# MAGIsDebugger.net
KiCad netlist of a schematic drawn in Altium Designer
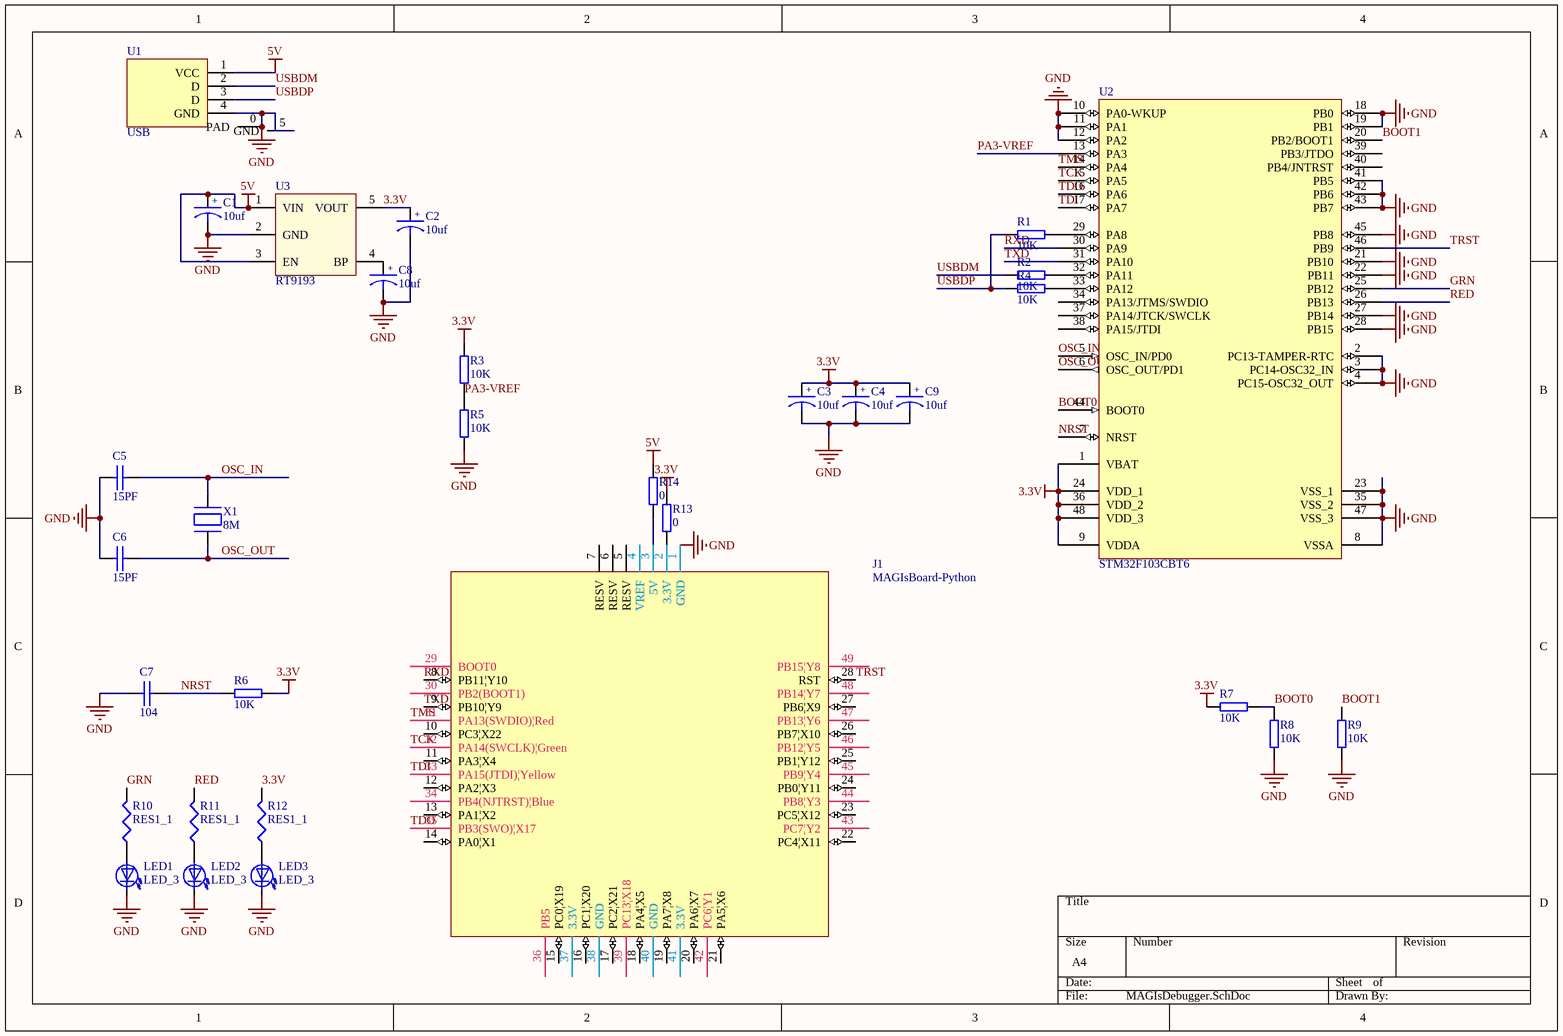
[diagram p0: MAGIsDebugger.SchDoc]

(export (version "E")
  (design (tool "Eeschema 10.0.6"))
  (components
    (comp (ref "C1")
      (value "10uf")
      (footprint "6-0805_n")
      (description "Capacitor")
      (libsource (lib "电容器") (part "CAPACITOR POL"))
    )
    (comp (ref "C2")
      (value "10uf")
      (footprint "6-0805_n")
      (description "Capacitor")
      (libsource (lib "电容器") (part "CAPACITOR POL"))
    )
    (comp (ref "C3")
      (value "10uf")
      (footprint "6-0805_n")
      (description "Capacitor")
      (libsource (lib "电容器") (part "CAPACITOR POL"))
    )
    (comp (ref "C4")
      (value "10uf")
      (footprint "6-0805_N")
      (description "Capacitor")
      (libsource (lib "电容器") (part "CAPACITOR POL"))
    )
    (comp (ref "C5") (value "15PF") (footprint "6-0805_n") (libsource (lib "STM32") (part "CAP")))
    (comp (ref "C6") (value "15PF") (footprint "6-0805_n") (libsource (lib "STM32") (part "CAP")))
    (comp (ref "C7") (value "104") (footprint "6-0805_n") (libsource (lib "STM32") (part "CAP")))
    (comp (ref "C8")
      (value "10uf")
      (footprint "6-0805_n")
      (description "Capacitor")
      (libsource (lib "电容器") (part "CAPACITOR POL"))
    )
    (comp (ref "C9")
      (value "10uf")
      (footprint "6-0805_N")
      (description "Capacitor")
      (libsource (lib "电容器") (part "CAPACITOR POL"))
    )
    (comp (ref "J1")
      (value "MAGIsBoard-Python")
      (footprint "MAGIsBoard-Python")
      (libsource (lib "MAGIsBoard") (part "MAGIsBoard-Python"))
    )
    (comp (ref "LED1") (value "LED_3") (footprint "6-0805_n") (libsource (lib "二极管") (part "LED_3")))
    (comp (ref "LED2") (value "LED_3") (footprint "6-0805_n") (libsource (lib "二极管") (part "LED_3")))
    (comp (ref "LED3") (value "LED_3") (footprint "6-0805_n") (libsource (lib "二极管") (part "LED_3")))
    (comp (ref "R1") (value "10K") (footprint "6-0805_n") (libsource (lib "STM32") (part "RES")))
    (comp (ref "R2") (value "10K") (footprint "6-0805_n") (libsource (lib "STM32") (part "RES")))
    (comp (ref "R3") (value "10K") (footprint "6-0805_n") (libsource (lib "STM32") (part "RES")))
    (comp (ref "R4") (value "10K") (footprint "6-0805_n") (libsource (lib "STM32") (part "RES")))
    (comp (ref "R5") (value "10K") (footprint "6-0805_n") (libsource (lib "STM32") (part "RES")))
    (comp (ref "R6") (value "10K") (footprint "6-0805_n") (libsource (lib "STM32") (part "RES")))
    (comp (ref "R7") (value "10K") (footprint "6-0805_n") (libsource (lib "STM32") (part "RES")))
    (comp (ref "R8") (value "10K") (footprint "6-0805_n") (libsource (lib "STM32") (part "RES")))
    (comp (ref "R9") (value "10K") (footprint "6-0805_n") (libsource (lib "STM32") (part "RES")))
    (comp (ref "R10") (value "RES1_1") (footprint "6-0805_n") (libsource (lib "电阻器") (part "RES1_1")))
    (comp (ref "R11") (value "RES1_1") (footprint "6-0805_n") (libsource (lib "电阻器") (part "RES1_1")))
    (comp (ref "R12") (value "RES1_1") (footprint "6-0805_n") (libsource (lib "电阻器") (part "RES1_1")))
    (comp (ref "R13") (value "0") (footprint "6-0805_n") (libsource (lib "STM32") (part "RES")))
    (comp (ref "R14") (value "0") (footprint "6-0805_n") (libsource (lib "STM32") (part "RES")))
    (comp (ref "U1") (value "USB") (footprint "MicroUSB-B") (libsource (lib "USB接口") (part "USB")))
    (comp (ref "U2")
      (value "STM32F103CBT6")
      (footprint "LQFP48_N")
      (description "STM32 ARM-based 32-bit MCU with 128 Kbytes Flash, 48-pin LQFP, Industrial Temperature")
      (fields (field (name "PUBLISHER") "Altium Limited"))
      (libsource (lib "ST Microcontroller 32-Bit STM32") (part "STM32F103CBT6"))
    )
    (comp (ref "U3") (value "RT9193") (footprint "RT9193") (libsource (lib "PMIC") (part "RT9193")))
    (comp (ref "X1") (value "8M") (footprint "5032") (libsource (lib "STM32") (part "CRYSTAL")))
  )
  (nets
    (net (code "1") (name "/BOOT0") (class "Default")
      (node (ref "R7") (pin "1") (pinfunction "1_1") (pintype "passive"))
      (node (ref "R8") (pin "2") (pinfunction "2_2") (pintype "passive"))
      (node (ref "U2") (pin "44") (pinfunction "BOOT0_44") (pintype "input"))
    )
    (net (code "2") (name "/BOOT1") (class "Default")
      (node (ref "R9") (pin "2") (pinfunction "2_2") (pintype "passive"))
      (node (ref "U2") (pin "20") (pinfunction "PB2/BOOT1_20") (pintype "bidirectional"))
    )
    (net (code "3") (name "/GRN") (class "Default")
      (node (ref "R10") (pin "2") (pinfunction "2_2") (pintype "passive"))
      (node (ref "U2") (pin "25") (pinfunction "PB12_25") (pintype "bidirectional"))
    )
    (net (code "4") (name "/NRST") (class "Default")
      (node (ref "C7") (pin "2") (pinfunction "2_2") (pintype "passive"))
      (node (ref "R6") (pin "1") (pinfunction "1_1") (pintype "passive"))
      (node (ref "U2") (pin "7") (pinfunction "NRST_7") (pintype "bidirectional"))
    )
    (net (code "5") (name "/OSC_IN") (class "Default")
      (node (ref "C5") (pin "2") (pinfunction "2_2") (pintype "passive"))
      (node (ref "U2") (pin "5") (pinfunction "OSC_IN/PD0_5") (pintype "input"))
      (node (ref "X1") (pin "1") (pinfunction "1_1") (pintype "passive"))
    )
    (net (code "6") (name "/OSC_OUT") (class "Default")
      (node (ref "C6") (pin "2") (pinfunction "2_2") (pintype "passive"))
      (node (ref "U2") (pin "6") (pinfunction "OSC_OUT/PD1_6") (pintype "output"))
      (node (ref "X1") (pin "2") (pinfunction "2_2") (pintype "passive"))
    )
    (net (code "7") (name "/PA3-VREF") (class "Default")
      (node (ref "R3") (pin "1") (pinfunction "1_1") (pintype "passive"))
      (node (ref "R5") (pin "2") (pinfunction "2_2") (pintype "passive"))
      (node (ref "U2") (pin "13") (pinfunction "PA3_13") (pintype "bidirectional"))
    )
    (net (code "8") (name "/RED") (class "Default")
      (node (ref "R11") (pin "2") (pinfunction "2_2") (pintype "passive"))
      (node (ref "U2") (pin "26") (pinfunction "PB13_26") (pintype "bidirectional"))
    )
    (net (code "9") (name "/RXD") (class "Default")
      (node (ref "J1") (pin "8") (pinfunction "PB11¦Y10_8") (pintype "bidirectional"))
      (node (ref "U2") (pin "30") (pinfunction "PA9_30") (pintype "bidirectional"))
    )
    (net (code "10") (name "/TCK") (class "Default")
      (node (ref "J1") (pin "32") (pinfunction "PA14(SWCLK)¦Green_32") (pintype "passive"))
      (node (ref "U2") (pin "15") (pinfunction "PA5_15") (pintype "bidirectional"))
    )
    (net (code "11") (name "/TDI") (class "Default")
      (node (ref "J1") (pin "33") (pinfunction "PA15(JTDI)¦Yellow_33") (pintype "passive"))
      (node (ref "U2") (pin "17") (pinfunction "PA7_17") (pintype "bidirectional"))
    )
    (net (code "12") (name "/TDO") (class "Default")
      (node (ref "J1") (pin "35") (pinfunction "PB3(SWO)¦X17_35") (pintype "passive"))
      (node (ref "U2") (pin "16") (pinfunction "PA6_16") (pintype "bidirectional"))
    )
    (net (code "13") (name "/TMS") (class "Default")
      (node (ref "J1") (pin "31") (pinfunction "PA13(SWDIO)¦Red_31") (pintype "passive"))
      (node (ref "U2") (pin "14") (pinfunction "PA4_14") (pintype "bidirectional"))
    )
    (net (code "14") (name "/TRST") (class "Default")
      (node (ref "J1") (pin "28") (pinfunction "RST_28") (pintype "bidirectional"))
      (node (ref "U2") (pin "46") (pinfunction "PB9_46") (pintype "bidirectional"))
    )
    (net (code "15") (name "/TXD") (class "Default")
      (node (ref "J1") (pin "9") (pinfunction "PB10¦Y9_9") (pintype "bidirectional"))
      (node (ref "U2") (pin "31") (pinfunction "PA10_31") (pintype "bidirectional"))
    )
    (net (code "16") (name "/USBDM") (class "Default")
      (node (ref "R2") (pin "1") (pinfunction "1_1") (pintype "passive"))
      (node (ref "U1") (pin "2") (pinfunction "D_2") (pintype "passive"))
    )
    (net (code "17") (name "/USBDP") (class "Default")
      (node (ref "R1") (pin "1") (pinfunction "1_1") (pintype "passive"))
      (node (ref "R4") (pin "1") (pinfunction "1_1") (pintype "passive"))
      (node (ref "U1") (pin "3") (pinfunction "D_3") (pintype "passive"))
    )
    (net (code "18") (name "3.3V") (class "Default")
      (node (ref "C2") (pin "1") (pinfunction "1_1") (pintype "passive"))
      (node (ref "C3") (pin "1") (pinfunction "1_1") (pintype "passive"))
      (node (ref "C4") (pin "1") (pinfunction "1_1") (pintype "passive"))
      (node (ref "C9") (pin "1") (pinfunction "1_1") (pintype "passive"))
      (node (ref "R12") (pin "2") (pinfunction "2_2") (pintype "passive"))
      (node (ref "R13") (pin "1") (pinfunction "1_1") (pintype "passive"))
      (node (ref "R3") (pin "2") (pinfunction "2_2") (pintype "passive"))
      (node (ref "R6") (pin "2") (pinfunction "2_2") (pintype "passive"))
      (node (ref "R7") (pin "2") (pinfunction "2_2") (pintype "passive"))
      (node (ref "U2") (pin "1") (pinfunction "VBAT_1") (pintype "power_in"))
      (node (ref "U2") (pin "24") (pinfunction "VDD_1_24") (pintype "power_in"))
      (node (ref "U2") (pin "36") (pinfunction "VDD_2_36") (pintype "power_in"))
      (node (ref "U2") (pin "48") (pinfunction "VDD_3_48") (pintype "power_in"))
      (node (ref "U2") (pin "9") (pinfunction "VDDA_9") (pintype "power_in"))
      (node (ref "U3") (pin "5") (pinfunction "VOUT_5") (pintype "passive"))
    )
    (net (code "19") (name "5V") (class "Default")
      (node (ref "C1") (pin "1") (pinfunction "1_1") (pintype "passive"))
      (node (ref "R14") (pin "1") (pinfunction "1_1") (pintype "passive"))
      (node (ref "U1") (pin "1") (pinfunction "VCC_1") (pintype "passive"))
      (node (ref "U3") (pin "1") (pinfunction "VIN_1") (pintype "passive"))
      (node (ref "U3") (pin "3") (pinfunction "EN_3") (pintype "passive"))
    )
    (net (code "20") (name "GND") (class "Default")
      (node (ref "C1") (pin "2") (pinfunction "2_2") (pintype "passive"))
      (node (ref "C2") (pin "2") (pinfunction "2_2") (pintype "passive"))
      (node (ref "C3") (pin "2") (pinfunction "2_2") (pintype "passive"))
      (node (ref "C4") (pin "2") (pinfunction "2_2") (pintype "passive"))
      (node (ref "C5") (pin "1") (pinfunction "1_1") (pintype "passive"))
      (node (ref "C6") (pin "1") (pinfunction "1_1") (pintype "passive"))
      (node (ref "C7") (pin "1") (pinfunction "1_1") (pintype "passive"))
      (node (ref "C8") (pin "2") (pinfunction "2_2") (pintype "passive"))
      (node (ref "C9") (pin "2") (pinfunction "2_2") (pintype "passive"))
      (node (ref "J1") (pin "1") (pinfunction "GND_1") (pintype "power_in"))
      (node (ref "LED1") (pin "2") (pinfunction "K_2") (pintype "passive"))
      (node (ref "LED2") (pin "2") (pinfunction "K_2") (pintype "passive"))
      (node (ref "LED3") (pin "2") (pinfunction "K_2") (pintype "passive"))
      (node (ref "R5") (pin "1") (pinfunction "1_1") (pintype "passive"))
      (node (ref "R8") (pin "1") (pinfunction "1_1") (pintype "passive"))
      (node (ref "R9") (pin "1") (pinfunction "1_1") (pintype "passive"))
      (node (ref "U1") (pin "0") (pinfunction "PAD_0") (pintype "passive"))
      (node (ref "U1") (pin "4") (pinfunction "GND_4") (pintype "passive"))
      (node (ref "U1") (pin "5") (pinfunction "GND_5") (pintype "passive"))
      (node (ref "U2") (pin "10") (pinfunction "PA0-WKUP_10") (pintype "bidirectional"))
      (node (ref "U2") (pin "11") (pinfunction "PA1_11") (pintype "bidirectional"))
      (node (ref "U2") (pin "12") (pinfunction "PA2_12") (pintype "bidirectional"))
      (node (ref "U2") (pin "18") (pinfunction "PB0_18") (pintype "bidirectional"))
      (node (ref "U2") (pin "19") (pinfunction "PB1_19") (pintype "bidirectional"))
      (node (ref "U2") (pin "2") (pinfunction "PC13-TAMPER-RTC_2") (pintype "bidirectional"))
      (node (ref "U2") (pin "21") (pinfunction "PB10_21") (pintype "bidirectional"))
      (node (ref "U2") (pin "22") (pinfunction "PB11_22") (pintype "bidirectional"))
      (node (ref "U2") (pin "23") (pinfunction "VSS_1_23") (pintype "power_in"))
      (node (ref "U2") (pin "27") (pinfunction "PB14_27") (pintype "bidirectional"))
      (node (ref "U2") (pin "28") (pinfunction "PB15_28") (pintype "bidirectional"))
      (node (ref "U2") (pin "3") (pinfunction "PC14-OSC32_IN_3") (pintype "bidirectional"))
      (node (ref "U2") (pin "35") (pinfunction "VSS_2_35") (pintype "power_in"))
      (node (ref "U2") (pin "4") (pinfunction "PC15-OSC32_OUT_4") (pintype "bidirectional"))
      (node (ref "U2") (pin "41") (pinfunction "PB5_41") (pintype "bidirectional"))
      (node (ref "U2") (pin "42") (pinfunction "PB6_42") (pintype "bidirectional"))
      (node (ref "U2") (pin "43") (pinfunction "PB7_43") (pintype "bidirectional"))
      (node (ref "U2") (pin "45") (pinfunction "PB8_45") (pintype "bidirectional"))
      (node (ref "U2") (pin "47") (pinfunction "VSS_3_47") (pintype "power_in"))
      (node (ref "U2") (pin "8") (pinfunction "VSSA_8") (pintype "power_in"))
      (node (ref "U3") (pin "2") (pinfunction "GND_2") (pintype "passive"))
    )
    (net (code "21") (name "Net-(J1-3.3V-Pad2)") (class "Default")
      (node (ref "J1") (pin "2") (pinfunction "3.3V_2") (pintype "power_in"))
      (node (ref "R13") (pin "2") (pinfunction "2_2") (pintype "passive"))
    )
    (net (code "22") (name "Net-(J1-5V)") (class "Default")
      (node (ref "J1") (pin "3") (pinfunction "5V_3") (pintype "power_in"))
      (node (ref "R14") (pin "2") (pinfunction "2_2") (pintype "passive"))
    )
    (net (code "23") (name "Net-(LED1-A)") (class "Default")
      (node (ref "LED1") (pin "1") (pinfunction "A_1") (pintype "passive"))
      (node (ref "R10") (pin "1") (pinfunction "1_1") (pintype "passive"))
    )
    (net (code "24") (name "Net-(LED2-A)") (class "Default")
      (node (ref "LED2") (pin "1") (pinfunction "A_1") (pintype "passive"))
      (node (ref "R11") (pin "1") (pinfunction "1_1") (pintype "passive"))
    )
    (net (code "25") (name "Net-(LED3-A)") (class "Default")
      (node (ref "LED3") (pin "1") (pinfunction "A_1") (pintype "passive"))
      (node (ref "R12") (pin "1") (pinfunction "1_1") (pintype "passive"))
    )
    (net (code "26") (name "Net-(U2-PA8)") (class "Default")
      (node (ref "R1") (pin "2") (pinfunction "2_2") (pintype "passive"))
      (node (ref "U2") (pin "29") (pinfunction "PA8_29") (pintype "bidirectional"))
    )
    (net (code "27") (name "Net-(U2-PA11)") (class "Default")
      (node (ref "R2") (pin "2") (pinfunction "2_2") (pintype "passive"))
      (node (ref "U2") (pin "32") (pinfunction "PA11_32") (pintype "bidirectional"))
    )
    (net (code "28") (name "Net-(U2-PA12)") (class "Default")
      (node (ref "R4") (pin "2") (pinfunction "2_2") (pintype "passive"))
      (node (ref "U2") (pin "33") (pinfunction "PA12_33") (pintype "bidirectional"))
    )
    (net (code "29") (name "Net-(U3-BP)") (class "Default")
      (node (ref "C8") (pin "1") (pinfunction "1_1") (pintype "passive"))
      (node (ref "U3") (pin "4") (pinfunction "BP_4") (pintype "passive"))
    )
    (net (code "30") (name "unconnected-(J1-3.3V-Pad37)") (class "Default")
      (node (ref "J1") (pin "37") (pinfunction "3.3V_37") (pintype "passive"))
    )
    (net (code "31") (name "unconnected-(J1-3.3V-Pad41)") (class "Default")
      (node (ref "J1") (pin "41") (pinfunction "3.3V_41") (pintype "passive"))
    )
    (net (code "32") (name "unconnected-(J1-BOOT0-Pad29)") (class "Default")
      (node (ref "J1") (pin "29") (pinfunction "BOOT0_29") (pintype "passive"))
    )
    (net (code "33") (name "unconnected-(J1-GND-Pad38)") (class "Default")
      (node (ref "J1") (pin "38") (pinfunction "GND_38") (pintype "passive"))
    )
    (net (code "34") (name "unconnected-(J1-GND-Pad40)") (class "Default")
      (node (ref "J1") (pin "40") (pinfunction "GND_40") (pintype "passive"))
    )
    (net (code "35") (name "unconnected-(J1-PA0¦X1-Pad14)") (class "Default")
      (node (ref "J1") (pin "14") (pinfunction "PA0¦X1_14") (pintype "bidirectional"))
    )
    (net (code "36") (name "unconnected-(J1-PA1¦X2-Pad13)") (class "Default")
      (node (ref "J1") (pin "13") (pinfunction "PA1¦X2_13") (pintype "bidirectional"))
    )
    (net (code "37") (name "unconnected-(J1-PA2¦X3-Pad12)") (class "Default")
      (node (ref "J1") (pin "12") (pinfunction "PA2¦X3_12") (pintype "bidirectional"))
    )
    (net (code "38") (name "unconnected-(J1-PA3¦X4-Pad11)") (class "Default")
      (node (ref "J1") (pin "11") (pinfunction "PA3¦X4_11") (pintype "bidirectional"))
    )
    (net (code "39") (name "unconnected-(J1-PA4¦X5-Pad18)") (class "Default")
      (node (ref "J1") (pin "18") (pinfunction "PA4¦X5_18") (pintype "bidirectional"))
    )
    (net (code "40") (name "unconnected-(J1-PA5¦X6-Pad21)") (class "Default")
      (node (ref "J1") (pin "21") (pinfunction "PA5¦X6_21") (pintype "bidirectional"))
    )
    (net (code "41") (name "unconnected-(J1-PA6¦X7-Pad20)") (class "Default")
      (node (ref "J1") (pin "20") (pinfunction "PA6¦X7_20") (pintype "bidirectional"))
    )
    (net (code "42") (name "unconnected-(J1-PA7¦X8-Pad19)") (class "Default")
      (node (ref "J1") (pin "19") (pinfunction "PA7¦X8_19") (pintype "bidirectional"))
    )
    (net (code "43") (name "unconnected-(J1-PB0¦Y11-Pad24)") (class "Default")
      (node (ref "J1") (pin "24") (pinfunction "PB0¦Y11_24") (pintype "bidirectional"))
    )
    (net (code "44") (name "unconnected-(J1-PB1¦Y12-Pad25)") (class "Default")
      (node (ref "J1") (pin "25") (pinfunction "PB1¦Y12_25") (pintype "bidirectional"))
    )
    (net (code "45") (name "unconnected-(J1-PB2(BOOT1)-Pad30)") (class "Default")
      (node (ref "J1") (pin "30") (pinfunction "PB2(BOOT1)_30") (pintype "passive"))
    )
    (net (code "46") (name "unconnected-(J1-PB4(NJTRST)¦Blue-Pad34)") (class "Default")
      (node (ref "J1") (pin "34") (pinfunction "PB4(NJTRST)¦Blue_34") (pintype "passive"))
    )
    (net (code "47") (name "unconnected-(J1-PB5-Pad36)") (class "Default")
      (node (ref "J1") (pin "36") (pinfunction "PB5_36") (pintype "passive"))
    )
    (net (code "48") (name "unconnected-(J1-PB6¦X9-Pad27)") (class "Default")
      (node (ref "J1") (pin "27") (pinfunction "PB6¦X9_27") (pintype "bidirectional"))
    )
    (net (code "49") (name "unconnected-(J1-PB7¦X10-Pad26)") (class "Default")
      (node (ref "J1") (pin "26") (pinfunction "PB7¦X10_26") (pintype "bidirectional"))
    )
    (net (code "50") (name "unconnected-(J1-PB8¦Y3-Pad44)") (class "Default")
      (node (ref "J1") (pin "44") (pinfunction "PB8¦Y3_44") (pintype "passive"))
    )
    (net (code "51") (name "unconnected-(J1-PB9¦Y4-Pad45)") (class "Default")
      (node (ref "J1") (pin "45") (pinfunction "PB9¦Y4_45") (pintype "passive"))
    )
    (net (code "52") (name "unconnected-(J1-PB12¦Y5-Pad46)") (class "Default")
      (node (ref "J1") (pin "46") (pinfunction "PB12¦Y5_46") (pintype "passive"))
    )
    (net (code "53") (name "unconnected-(J1-PB13¦Y6-Pad47)") (class "Default")
      (node (ref "J1") (pin "47") (pinfunction "PB13¦Y6_47") (pintype "passive"))
    )
    (net (code "54") (name "unconnected-(J1-PB14¦Y7-Pad48)") (class "Default")
      (node (ref "J1") (pin "48") (pinfunction "PB14¦Y7_48") (pintype "passive"))
    )
    (net (code "55") (name "unconnected-(J1-PB15¦Y8-Pad49)") (class "Default")
      (node (ref "J1") (pin "49") (pinfunction "PB15¦Y8_49") (pintype "passive"))
    )
    (net (code "56") (name "unconnected-(J1-PC0¦X19-Pad15)") (class "Default")
      (node (ref "J1") (pin "15") (pinfunction "PC0¦X19_15") (pintype "bidirectional"))
    )
    (net (code "57") (name "unconnected-(J1-PC1¦X20-Pad16)") (class "Default")
      (node (ref "J1") (pin "16") (pinfunction "PC1¦X20_16") (pintype "bidirectional"))
    )
    (net (code "58") (name "unconnected-(J1-PC2¦X21-Pad17)") (class "Default")
      (node (ref "J1") (pin "17") (pinfunction "PC2¦X21_17") (pintype "bidirectional"))
    )
    (net (code "59") (name "unconnected-(J1-PC3¦X22-Pad10)") (class "Default")
      (node (ref "J1") (pin "10") (pinfunction "PC3¦X22_10") (pintype "bidirectional"))
    )
    (net (code "60") (name "unconnected-(J1-PC4¦X11-Pad22)") (class "Default")
      (node (ref "J1") (pin "22") (pinfunction "PC4¦X11_22") (pintype "bidirectional"))
    )
    (net (code "61") (name "unconnected-(J1-PC5¦X12-Pad23)") (class "Default")
      (node (ref "J1") (pin "23") (pinfunction "PC5¦X12_23") (pintype "bidirectional"))
    )
    (net (code "62") (name "unconnected-(J1-PC6¦Y1-Pad42)") (class "Default")
      (node (ref "J1") (pin "42") (pinfunction "PC6¦Y1_42") (pintype "passive"))
    )
    (net (code "63") (name "unconnected-(J1-PC7¦Y2-Pad43)") (class "Default")
      (node (ref "J1") (pin "43") (pinfunction "PC7¦Y2_43") (pintype "passive"))
    )
    (net (code "64") (name "unconnected-(J1-PC13¦X18-Pad39)") (class "Default")
      (node (ref "J1") (pin "39") (pinfunction "PC13¦X18_39") (pintype "passive"))
    )
    (net (code "65") (name "unconnected-(J1-RESV-Pad5)") (class "Default")
      (node (ref "J1") (pin "5") (pinfunction "RESV_5") (pintype "passive"))
    )
    (net (code "66") (name "unconnected-(J1-RESV-Pad6)") (class "Default")
      (node (ref "J1") (pin "6") (pinfunction "RESV_6") (pintype "passive"))
    )
    (net (code "67") (name "unconnected-(J1-RESV-Pad7)") (class "Default")
      (node (ref "J1") (pin "7") (pinfunction "RESV_7") (pintype "passive"))
    )
    (net (code "68") (name "unconnected-(J1-VREF-Pad4)") (class "Default")
      (node (ref "J1") (pin "4") (pinfunction "VREF_4") (pintype "passive"))
    )
    (net (code "69") (name "unconnected-(U2-PA13{slash}JTMS{slash}SWDIO-Pad34)") (class "Default")
      (node (ref "U2") (pin "34") (pinfunction "PA13/JTMS/SWDIO_34") (pintype "bidirectional"))
    )
    (net (code "70") (name "unconnected-(U2-PA14{slash}JTCK{slash}SWCLK-Pad37)") (class "Default")
      (node (ref "U2") (pin "37") (pinfunction "PA14/JTCK/SWCLK_37") (pintype "bidirectional"))
    )
    (net (code "71") (name "unconnected-(U2-PA15{slash}JTDI-Pad38)") (class "Default")
      (node (ref "U2") (pin "38") (pinfunction "PA15/JTDI_38") (pintype "bidirectional"))
    )
    (net (code "72") (name "unconnected-(U2-PB3{slash}JTDO-Pad39)") (class "Default")
      (node (ref "U2") (pin "39") (pinfunction "PB3/JTDO_39") (pintype "bidirectional"))
    )
    (net (code "73") (name "unconnected-(U2-PB4{slash}JNTRST-Pad40)") (class "Default")
      (node (ref "U2") (pin "40") (pinfunction "PB4/JNTRST_40") (pintype "bidirectional"))
    )
  )
)
